# Game_Board.net
KiCad netlist of a schematic drawn in EAGLE
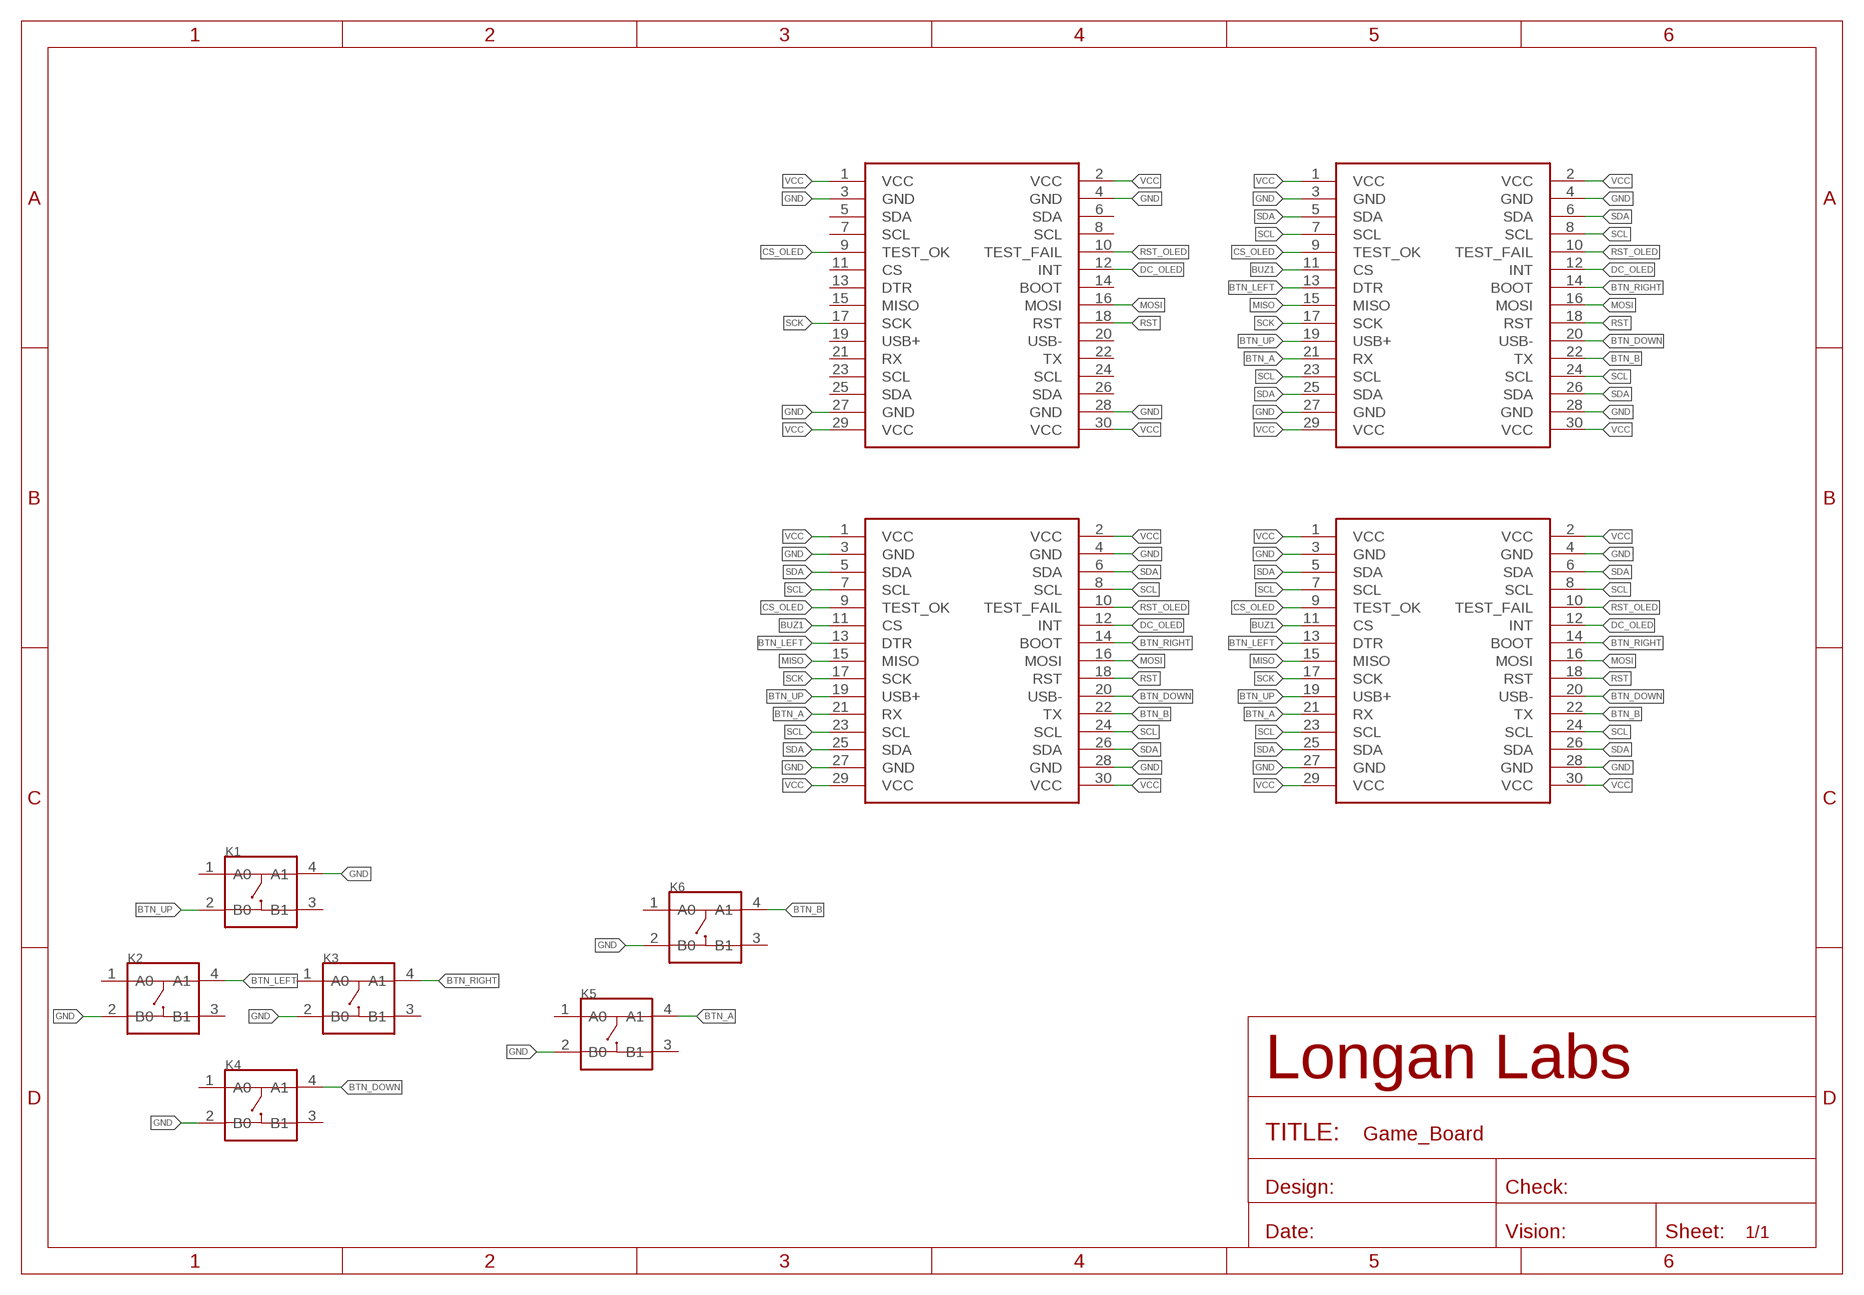
[diagram p0: schematic, sheet 1]

(export (version "E")
  (design (tool "Eeschema 10.0.6"))
  (components
    (comp (ref "K1")
      (value "BUTTON-4PDTSM-62K-S-V-T/R(SN431)")
      (footprint "eagle-import:SW4-SMD-6.0X6.0X5.0MM")
      (libsource (lib "eagle-import") (part "BUTTON-4PDTSM-62K-S-V-T/R(SN431)"))
    )
    (comp (ref "K2")
      (value "BUTTON-4PDTSM-62K-S-V-T/R(SN431)")
      (footprint "eagle-import:SW4-SMD-6.0X6.0X5.0MM")
      (libsource (lib "eagle-import") (part "BUTTON-4PDTSM-62K-S-V-T/R(SN431)"))
    )
    (comp (ref "K3")
      (value "BUTTON-4PDTSM-62K-S-V-T/R(SN431)")
      (footprint "eagle-import:SW4-SMD-6.0X6.0X5.0MM")
      (libsource (lib "eagle-import") (part "BUTTON-4PDTSM-62K-S-V-T/R(SN431)"))
    )
    (comp (ref "K4")
      (value "BUTTON-4PDTSM-62K-S-V-T/R(SN431)")
      (footprint "eagle-import:SW4-SMD-6.0X6.0X5.0MM")
      (libsource (lib "eagle-import") (part "BUTTON-4PDTSM-62K-S-V-T/R(SN431)"))
    )
    (comp (ref "K5")
      (value "BUTTON-4PDTSM-62K-S-V-T/R(SN431)")
      (footprint "eagle-import:SW4-SMD-6.0X6.0X5.0MM")
      (libsource (lib "eagle-import") (part "BUTTON-4PDTSM-62K-S-V-T/R(SN431)"))
    )
    (comp (ref "K6")
      (value "BUTTON-4PDTSM-62K-S-V-T/R(SN431)")
      (footprint "eagle-import:SW4-SMD-6.0X6.0X5.0MM")
      (libsource (lib "eagle-import") (part "BUTTON-4PDTSM-62K-S-V-T/R(SN431)"))
    )
    (comp (ref "MOUDLE1")
      (value "MOUDLE-2X15P-2.54'2.54'")
      (footprint "eagle-import:2X15P-2.54")
      (libsource (lib "eagle-import") (part "MOUDLE-2X15P-2.54'2.54'"))
    )
    (comp (ref "MOUDLE2")
      (value "MOUDLE-2X15P-2.54'2.54'")
      (footprint "eagle-import:2X15P-2.54")
      (libsource (lib "eagle-import") (part "MOUDLE-2X15P-2.54'2.54'"))
    )
    (comp (ref "MOUDLE3")
      (value "MOUDLE-2X15P-2.54'90D'")
      (footprint "eagle-import:2X15P-2.54-90D")
      (libsource (lib "eagle-import") (part "MOUDLE-2X15P-2.54'90D'"))
    )
    (comp (ref "MOUDLE4")
      (value "MOUDLE-2X15P-2.54'2.54'")
      (footprint "eagle-import:2X15P-2.54")
      (libsource (lib "eagle-import") (part "MOUDLE-2X15P-2.54'2.54'"))
    )
  )
  (nets
    (net (code "1") (name "BTN_A") (class "Default")
      (node (ref "K5") (pin "4") (pinfunction "A1_4") (pintype "bidirectional"))
      (node (ref "MOUDLE1") (pin "21") (pinfunction "RX_21") (pintype "bidirectional"))
      (node (ref "MOUDLE2") (pin "21") (pinfunction "RX_21") (pintype "bidirectional"))
      (node (ref "MOUDLE4") (pin "21") (pinfunction "RX_21") (pintype "bidirectional"))
    )
    (net (code "2") (name "BTN_B") (class "Default")
      (node (ref "K6") (pin "4") (pinfunction "A1_4") (pintype "bidirectional"))
      (node (ref "MOUDLE1") (pin "22") (pinfunction "TX_22") (pintype "bidirectional"))
      (node (ref "MOUDLE2") (pin "22") (pinfunction "TX_22") (pintype "bidirectional"))
      (node (ref "MOUDLE4") (pin "22") (pinfunction "TX_22") (pintype "bidirectional"))
    )
    (net (code "3") (name "BTN_DOWN") (class "Default")
      (node (ref "K4") (pin "4") (pinfunction "A1_4") (pintype "bidirectional"))
      (node (ref "MOUDLE1") (pin "20") (pinfunction "USB-_20") (pintype "bidirectional"))
      (node (ref "MOUDLE2") (pin "20") (pinfunction "USB-_20") (pintype "bidirectional"))
      (node (ref "MOUDLE4") (pin "20") (pinfunction "USB-_20") (pintype "bidirectional"))
    )
    (net (code "4") (name "BTN_LEFT") (class "Default")
      (node (ref "K2") (pin "4") (pinfunction "A1_4") (pintype "bidirectional"))
      (node (ref "MOUDLE1") (pin "13") (pinfunction "DTR_13") (pintype "bidirectional"))
      (node (ref "MOUDLE2") (pin "13") (pinfunction "DTR_13") (pintype "bidirectional"))
      (node (ref "MOUDLE4") (pin "13") (pinfunction "DTR_13") (pintype "bidirectional"))
    )
    (net (code "5") (name "BTN_RIGHT") (class "Default")
      (node (ref "K3") (pin "4") (pinfunction "A1_4") (pintype "bidirectional"))
      (node (ref "MOUDLE1") (pin "14") (pinfunction "BOOT_14") (pintype "bidirectional"))
      (node (ref "MOUDLE2") (pin "14") (pinfunction "BOOT_14") (pintype "bidirectional"))
      (node (ref "MOUDLE4") (pin "14") (pinfunction "BOOT_14") (pintype "bidirectional"))
    )
    (net (code "6") (name "BTN_UP") (class "Default")
      (node (ref "K1") (pin "2") (pinfunction "B0_2") (pintype "bidirectional"))
      (node (ref "MOUDLE1") (pin "19") (pinfunction "USB+_19") (pintype "bidirectional"))
      (node (ref "MOUDLE2") (pin "19") (pinfunction "USB+_19") (pintype "bidirectional"))
      (node (ref "MOUDLE4") (pin "19") (pinfunction "USB+_19") (pintype "bidirectional"))
    )
    (net (code "7") (name "BUZ1") (class "Default")
      (node (ref "MOUDLE1") (pin "11") (pinfunction "CS_11") (pintype "bidirectional"))
      (node (ref "MOUDLE2") (pin "11") (pinfunction "CS_11") (pintype "bidirectional"))
      (node (ref "MOUDLE4") (pin "11") (pinfunction "CS_11") (pintype "bidirectional"))
    )
    (net (code "8") (name "CS_OLED") (class "Default")
      (node (ref "MOUDLE1") (pin "9") (pinfunction "TEST_OK_9") (pintype "bidirectional"))
      (node (ref "MOUDLE2") (pin "9") (pinfunction "TEST_OK_9") (pintype "bidirectional"))
      (node (ref "MOUDLE3") (pin "9") (pinfunction "TEST_OK_9") (pintype "bidirectional"))
      (node (ref "MOUDLE4") (pin "9") (pinfunction "TEST_OK_9") (pintype "bidirectional"))
    )
    (net (code "9") (name "DC_OLED") (class "Default")
      (node (ref "MOUDLE1") (pin "12") (pinfunction "INT_12") (pintype "bidirectional"))
      (node (ref "MOUDLE2") (pin "12") (pinfunction "INT_12") (pintype "bidirectional"))
      (node (ref "MOUDLE3") (pin "12") (pinfunction "INT_12") (pintype "bidirectional"))
      (node (ref "MOUDLE4") (pin "12") (pinfunction "INT_12") (pintype "bidirectional"))
    )
    (net (code "10") (name "GND") (class "Default")
      (node (ref "K1") (pin "4") (pinfunction "A1_4") (pintype "bidirectional"))
      (node (ref "K2") (pin "2") (pinfunction "B0_2") (pintype "bidirectional"))
      (node (ref "K3") (pin "2") (pinfunction "B0_2") (pintype "bidirectional"))
      (node (ref "K4") (pin "2") (pinfunction "B0_2") (pintype "bidirectional"))
      (node (ref "K5") (pin "2") (pinfunction "B0_2") (pintype "bidirectional"))
      (node (ref "K6") (pin "2") (pinfunction "B0_2") (pintype "bidirectional"))
      (node (ref "MOUDLE1") (pin "27") (pinfunction "GND_27") (pintype "bidirectional"))
      (node (ref "MOUDLE1") (pin "28") (pinfunction "GND_28") (pintype "bidirectional"))
      (node (ref "MOUDLE1") (pin "3") (pinfunction "GND_3") (pintype "bidirectional"))
      (node (ref "MOUDLE1") (pin "4") (pinfunction "GND_4") (pintype "bidirectional"))
      (node (ref "MOUDLE2") (pin "27") (pinfunction "GND_27") (pintype "bidirectional"))
      (node (ref "MOUDLE2") (pin "28") (pinfunction "GND_28") (pintype "bidirectional"))
      (node (ref "MOUDLE2") (pin "3") (pinfunction "GND_3") (pintype "bidirectional"))
      (node (ref "MOUDLE2") (pin "4") (pinfunction "GND_4") (pintype "bidirectional"))
      (node (ref "MOUDLE3") (pin "27") (pinfunction "GND_27") (pintype "bidirectional"))
      (node (ref "MOUDLE3") (pin "28") (pinfunction "GND_28") (pintype "bidirectional"))
      (node (ref "MOUDLE3") (pin "3") (pinfunction "GND_3") (pintype "bidirectional"))
      (node (ref "MOUDLE3") (pin "4") (pinfunction "GND_4") (pintype "bidirectional"))
      (node (ref "MOUDLE4") (pin "27") (pinfunction "GND_27") (pintype "bidirectional"))
      (node (ref "MOUDLE4") (pin "28") (pinfunction "GND_28") (pintype "bidirectional"))
      (node (ref "MOUDLE4") (pin "3") (pinfunction "GND_3") (pintype "bidirectional"))
      (node (ref "MOUDLE4") (pin "4") (pinfunction "GND_4") (pintype "bidirectional"))
    )
    (net (code "11") (name "MISO") (class "Default")
      (node (ref "MOUDLE1") (pin "15") (pinfunction "MISO_15") (pintype "bidirectional"))
      (node (ref "MOUDLE2") (pin "15") (pinfunction "MISO_15") (pintype "bidirectional"))
      (node (ref "MOUDLE4") (pin "15") (pinfunction "MISO_15") (pintype "bidirectional"))
    )
    (net (code "12") (name "MOSI") (class "Default")
      (node (ref "MOUDLE1") (pin "16") (pinfunction "MOSI_16") (pintype "bidirectional"))
      (node (ref "MOUDLE2") (pin "16") (pinfunction "MOSI_16") (pintype "bidirectional"))
      (node (ref "MOUDLE3") (pin "16") (pinfunction "MOSI_16") (pintype "bidirectional"))
      (node (ref "MOUDLE4") (pin "16") (pinfunction "MOSI_16") (pintype "bidirectional"))
    )
    (net (code "13") (name "RST") (class "Default")
      (node (ref "MOUDLE1") (pin "18") (pinfunction "RST_18") (pintype "bidirectional"))
      (node (ref "MOUDLE2") (pin "18") (pinfunction "RST_18") (pintype "bidirectional"))
      (node (ref "MOUDLE3") (pin "18") (pinfunction "RST_18") (pintype "bidirectional"))
      (node (ref "MOUDLE4") (pin "18") (pinfunction "RST_18") (pintype "bidirectional"))
    )
    (net (code "14") (name "RST_OLED") (class "Default")
      (node (ref "MOUDLE1") (pin "10") (pinfunction "TEST_FAIL_10") (pintype "bidirectional"))
      (node (ref "MOUDLE2") (pin "10") (pinfunction "TEST_FAIL_10") (pintype "bidirectional"))
      (node (ref "MOUDLE3") (pin "10") (pinfunction "TEST_FAIL_10") (pintype "bidirectional"))
      (node (ref "MOUDLE4") (pin "10") (pinfunction "TEST_FAIL_10") (pintype "bidirectional"))
    )
    (net (code "15") (name "SCK") (class "Default")
      (node (ref "MOUDLE1") (pin "17") (pinfunction "SCK_17") (pintype "bidirectional"))
      (node (ref "MOUDLE2") (pin "17") (pinfunction "SCK_17") (pintype "bidirectional"))
      (node (ref "MOUDLE3") (pin "17") (pinfunction "SCK_17") (pintype "bidirectional"))
      (node (ref "MOUDLE4") (pin "17") (pinfunction "SCK_17") (pintype "bidirectional"))
    )
    (net (code "16") (name "SCL") (class "Default")
      (node (ref "MOUDLE1") (pin "23") (pinfunction "SCL_23") (pintype "bidirectional"))
      (node (ref "MOUDLE1") (pin "24") (pinfunction "SCL_24") (pintype "bidirectional"))
      (node (ref "MOUDLE1") (pin "7") (pinfunction "SCL_7") (pintype "bidirectional"))
      (node (ref "MOUDLE1") (pin "8") (pinfunction "SCL_8") (pintype "bidirectional"))
      (node (ref "MOUDLE2") (pin "23") (pinfunction "SCL_23") (pintype "bidirectional"))
      (node (ref "MOUDLE2") (pin "24") (pinfunction "SCL_24") (pintype "bidirectional"))
      (node (ref "MOUDLE2") (pin "7") (pinfunction "SCL_7") (pintype "bidirectional"))
      (node (ref "MOUDLE2") (pin "8") (pinfunction "SCL_8") (pintype "bidirectional"))
      (node (ref "MOUDLE4") (pin "23") (pinfunction "SCL_23") (pintype "bidirectional"))
      (node (ref "MOUDLE4") (pin "24") (pinfunction "SCL_24") (pintype "bidirectional"))
      (node (ref "MOUDLE4") (pin "7") (pinfunction "SCL_7") (pintype "bidirectional"))
      (node (ref "MOUDLE4") (pin "8") (pinfunction "SCL_8") (pintype "bidirectional"))
    )
    (net (code "17") (name "SDA") (class "Default")
      (node (ref "MOUDLE1") (pin "25") (pinfunction "SDA_25") (pintype "bidirectional"))
      (node (ref "MOUDLE1") (pin "26") (pinfunction "SDA_26") (pintype "bidirectional"))
      (node (ref "MOUDLE1") (pin "5") (pinfunction "SDA_5") (pintype "bidirectional"))
      (node (ref "MOUDLE1") (pin "6") (pinfunction "SDA_6") (pintype "bidirectional"))
      (node (ref "MOUDLE2") (pin "25") (pinfunction "SDA_25") (pintype "bidirectional"))
      (node (ref "MOUDLE2") (pin "26") (pinfunction "SDA_26") (pintype "bidirectional"))
      (node (ref "MOUDLE2") (pin "5") (pinfunction "SDA_5") (pintype "bidirectional"))
      (node (ref "MOUDLE2") (pin "6") (pinfunction "SDA_6") (pintype "bidirectional"))
      (node (ref "MOUDLE4") (pin "25") (pinfunction "SDA_25") (pintype "bidirectional"))
      (node (ref "MOUDLE4") (pin "26") (pinfunction "SDA_26") (pintype "bidirectional"))
      (node (ref "MOUDLE4") (pin "5") (pinfunction "SDA_5") (pintype "bidirectional"))
      (node (ref "MOUDLE4") (pin "6") (pinfunction "SDA_6") (pintype "bidirectional"))
    )
    (net (code "18") (name "VCC") (class "Default")
      (node (ref "MOUDLE1") (pin "1") (pinfunction "VCC_1") (pintype "bidirectional"))
      (node (ref "MOUDLE1") (pin "2") (pinfunction "VCC_2") (pintype "bidirectional"))
      (node (ref "MOUDLE1") (pin "29") (pinfunction "VCC_29") (pintype "bidirectional"))
      (node (ref "MOUDLE1") (pin "30") (pinfunction "VCC_30") (pintype "bidirectional"))
      (node (ref "MOUDLE2") (pin "1") (pinfunction "VCC_1") (pintype "bidirectional"))
      (node (ref "MOUDLE2") (pin "2") (pinfunction "VCC_2") (pintype "bidirectional"))
      (node (ref "MOUDLE2") (pin "29") (pinfunction "VCC_29") (pintype "bidirectional"))
      (node (ref "MOUDLE2") (pin "30") (pinfunction "VCC_30") (pintype "bidirectional"))
      (node (ref "MOUDLE3") (pin "1") (pinfunction "VCC_1") (pintype "bidirectional"))
      (node (ref "MOUDLE3") (pin "2") (pinfunction "VCC_2") (pintype "bidirectional"))
      (node (ref "MOUDLE3") (pin "29") (pinfunction "VCC_29") (pintype "bidirectional"))
      (node (ref "MOUDLE3") (pin "30") (pinfunction "VCC_30") (pintype "bidirectional"))
      (node (ref "MOUDLE4") (pin "1") (pinfunction "VCC_1") (pintype "bidirectional"))
      (node (ref "MOUDLE4") (pin "2") (pinfunction "VCC_2") (pintype "bidirectional"))
      (node (ref "MOUDLE4") (pin "29") (pinfunction "VCC_29") (pintype "bidirectional"))
      (node (ref "MOUDLE4") (pin "30") (pinfunction "VCC_30") (pintype "bidirectional"))
    )
    (net (code "19") (name "unconnected-(K1-A0-Pad1)") (class "Default")
      (node (ref "K1") (pin "1") (pinfunction "A0_1") (pintype "bidirectional"))
    )
    (net (code "20") (name "unconnected-(K1-B1-Pad3)") (class "Default")
      (node (ref "K1") (pin "3") (pinfunction "B1_3") (pintype "bidirectional"))
    )
    (net (code "21") (name "unconnected-(K2-A0-Pad1)") (class "Default")
      (node (ref "K2") (pin "1") (pinfunction "A0_1") (pintype "bidirectional"))
    )
    (net (code "22") (name "unconnected-(K2-B1-Pad3)") (class "Default")
      (node (ref "K2") (pin "3") (pinfunction "B1_3") (pintype "bidirectional"))
    )
    (net (code "23") (name "unconnected-(K3-A0-Pad1)") (class "Default")
      (node (ref "K3") (pin "1") (pinfunction "A0_1") (pintype "bidirectional"))
    )
    (net (code "24") (name "unconnected-(K3-B1-Pad3)") (class "Default")
      (node (ref "K3") (pin "3") (pinfunction "B1_3") (pintype "bidirectional"))
    )
    (net (code "25") (name "unconnected-(K4-A0-Pad1)") (class "Default")
      (node (ref "K4") (pin "1") (pinfunction "A0_1") (pintype "bidirectional"))
    )
    (net (code "26") (name "unconnected-(K4-B1-Pad3)") (class "Default")
      (node (ref "K4") (pin "3") (pinfunction "B1_3") (pintype "bidirectional"))
    )
    (net (code "27") (name "unconnected-(K5-A0-Pad1)") (class "Default")
      (node (ref "K5") (pin "1") (pinfunction "A0_1") (pintype "bidirectional"))
    )
    (net (code "28") (name "unconnected-(K5-B1-Pad3)") (class "Default")
      (node (ref "K5") (pin "3") (pinfunction "B1_3") (pintype "bidirectional"))
    )
    (net (code "29") (name "unconnected-(K6-A0-Pad1)") (class "Default")
      (node (ref "K6") (pin "1") (pinfunction "A0_1") (pintype "bidirectional"))
    )
    (net (code "30") (name "unconnected-(K6-B1-Pad3)") (class "Default")
      (node (ref "K6") (pin "3") (pinfunction "B1_3") (pintype "bidirectional"))
    )
    (net (code "31") (name "unconnected-(MOUDLE3-BOOT-Pad14)") (class "Default")
      (node (ref "MOUDLE3") (pin "14") (pinfunction "BOOT_14") (pintype "bidirectional"))
    )
    (net (code "32") (name "unconnected-(MOUDLE3-CS-Pad11)") (class "Default")
      (node (ref "MOUDLE3") (pin "11") (pinfunction "CS_11") (pintype "bidirectional"))
    )
    (net (code "33") (name "unconnected-(MOUDLE3-DTR-Pad13)") (class "Default")
      (node (ref "MOUDLE3") (pin "13") (pinfunction "DTR_13") (pintype "bidirectional"))
    )
    (net (code "34") (name "unconnected-(MOUDLE3-MISO-Pad15)") (class "Default")
      (node (ref "MOUDLE3") (pin "15") (pinfunction "MISO_15") (pintype "bidirectional"))
    )
    (net (code "35") (name "unconnected-(MOUDLE3-RX-Pad21)") (class "Default")
      (node (ref "MOUDLE3") (pin "21") (pinfunction "RX_21") (pintype "bidirectional"))
    )
    (net (code "36") (name "unconnected-(MOUDLE3-SCL-Pad7)") (class "Default")
      (node (ref "MOUDLE3") (pin "7") (pinfunction "SCL_7") (pintype "bidirectional"))
    )
    (net (code "37") (name "unconnected-(MOUDLE3-SCL-Pad8)") (class "Default")
      (node (ref "MOUDLE3") (pin "8") (pinfunction "SCL_8") (pintype "bidirectional"))
    )
    (net (code "38") (name "unconnected-(MOUDLE3-SCL-Pad23)") (class "Default")
      (node (ref "MOUDLE3") (pin "23") (pinfunction "SCL_23") (pintype "bidirectional"))
    )
    (net (code "39") (name "unconnected-(MOUDLE3-SCL-Pad24)") (class "Default")
      (node (ref "MOUDLE3") (pin "24") (pinfunction "SCL_24") (pintype "bidirectional"))
    )
    (net (code "40") (name "unconnected-(MOUDLE3-SDA-Pad5)") (class "Default")
      (node (ref "MOUDLE3") (pin "5") (pinfunction "SDA_5") (pintype "bidirectional"))
    )
    (net (code "41") (name "unconnected-(MOUDLE3-SDA-Pad6)") (class "Default")
      (node (ref "MOUDLE3") (pin "6") (pinfunction "SDA_6") (pintype "bidirectional"))
    )
    (net (code "42") (name "unconnected-(MOUDLE3-SDA-Pad25)") (class "Default")
      (node (ref "MOUDLE3") (pin "25") (pinfunction "SDA_25") (pintype "bidirectional"))
    )
    (net (code "43") (name "unconnected-(MOUDLE3-SDA-Pad26)") (class "Default")
      (node (ref "MOUDLE3") (pin "26") (pinfunction "SDA_26") (pintype "bidirectional"))
    )
    (net (code "44") (name "unconnected-(MOUDLE3-TX-Pad22)") (class "Default")
      (node (ref "MOUDLE3") (pin "22") (pinfunction "TX_22") (pintype "bidirectional"))
    )
    (net (code "45") (name "unconnected-(MOUDLE3-USB+-Pad19)") (class "Default")
      (node (ref "MOUDLE3") (pin "19") (pinfunction "USB+_19") (pintype "bidirectional"))
    )
    (net (code "46") (name "unconnected-(MOUDLE3-USB--Pad20)") (class "Default")
      (node (ref "MOUDLE3") (pin "20") (pinfunction "USB-_20") (pintype "bidirectional"))
    )
  )
)
